# Bending_Machine_SCH.net
KiCad netlist of a schematic drawn in Altium Designer
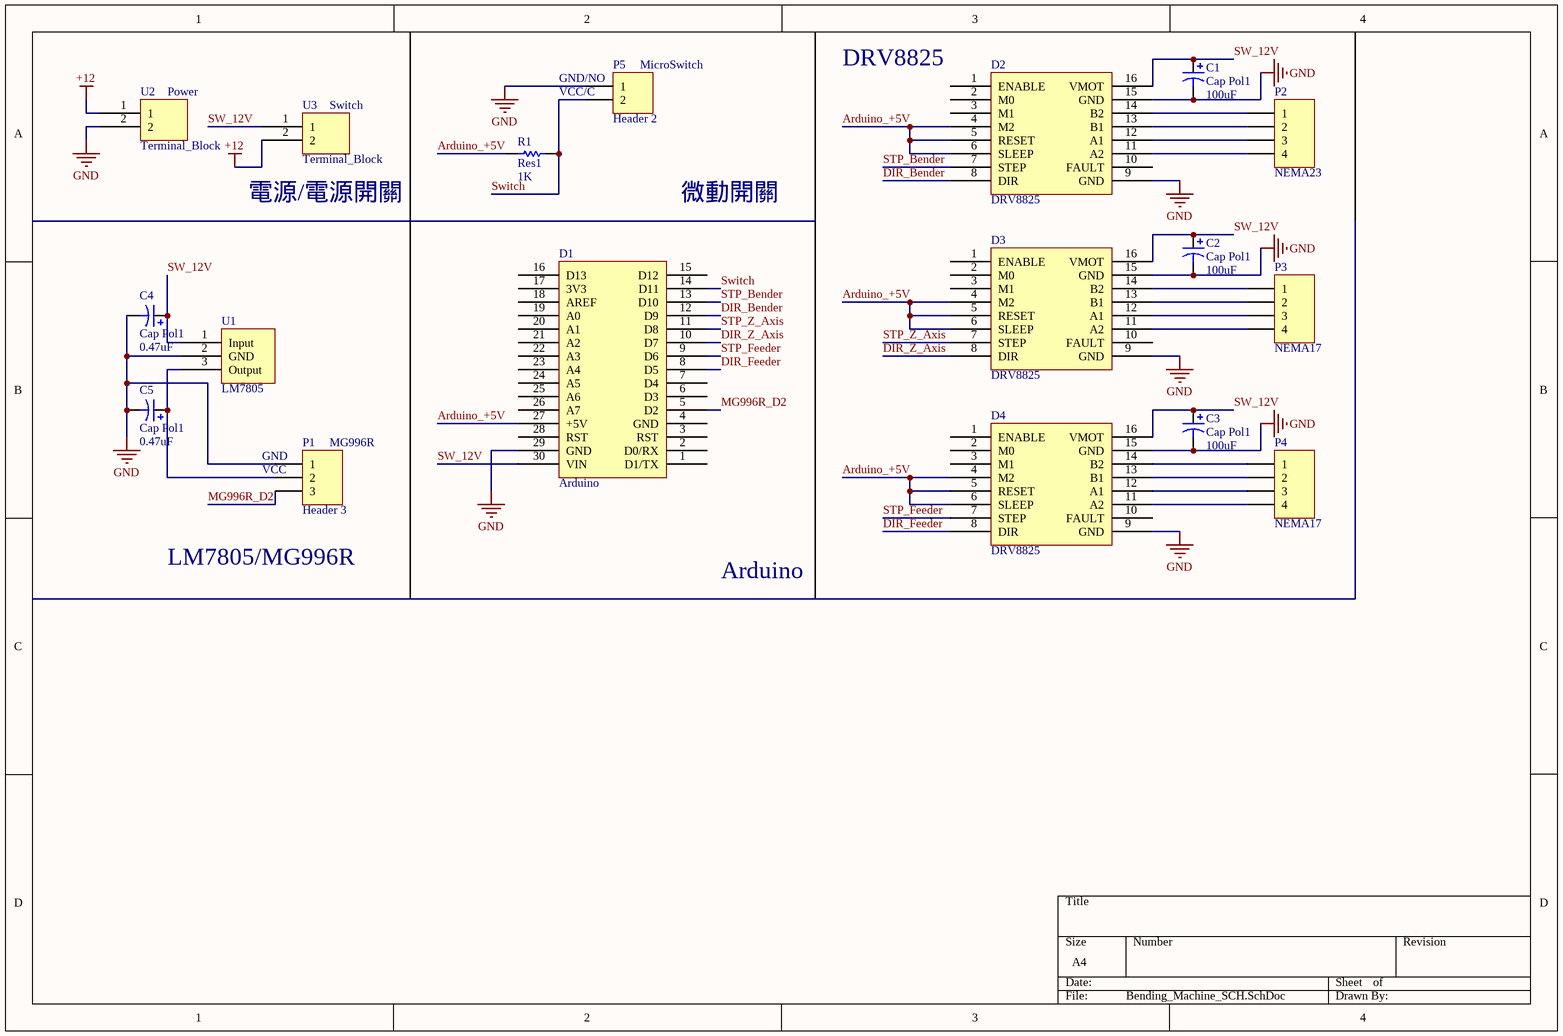
[diagram p0: Bending_Machine_SCH.SchDoc]

(export (version "E")
  (design (tool "Eeschema 10.0.6"))
  (components
    (comp (ref "C1")
      (value "Cap Pol1")
      (footprint "Cap_100uF")
      (description "Polarized Capacitor (Radial)")
      (fields (field (name "ALTIUM_VALUE") "100uF") (field (name "PUBLISHER") "Altium Limited"))
      (libsource (lib "Miscellaneous Devices") (part "Cap Pol1"))
    )
    (comp (ref "C2")
      (value "Cap Pol1")
      (footprint "Cap_100uF")
      (description "Polarized Capacitor (Radial)")
      (fields (field (name "ALTIUM_VALUE") "100uF") (field (name "PUBLISHER") "Altium Limited"))
      (libsource (lib "Miscellaneous Devices") (part "Cap Pol1"))
    )
    (comp (ref "C3")
      (value "Cap Pol1")
      (footprint "Cap_100uF")
      (description "Polarized Capacitor (Radial)")
      (fields (field (name "ALTIUM_VALUE") "100uF") (field (name "PUBLISHER") "Altium Limited"))
      (libsource (lib "Miscellaneous Devices") (part "Cap Pol1"))
    )
    (comp (ref "C4")
      (value "Cap Pol1")
      (footprint "Cap_0.47uF")
      (description "Polarized Capacitor (Radial)")
      (fields (field (name "ALTIUM_VALUE") "0.47uF") (field (name "PUBLISHER") "Altium Limited"))
      (libsource (lib "Miscellaneous Devices") (part "Cap Pol1"))
    )
    (comp (ref "C5")
      (value "Cap Pol1")
      (footprint "Cap_0.47uF")
      (description "Polarized Capacitor (Radial)")
      (fields (field (name "ALTIUM_VALUE") "0.47uF") (field (name "PUBLISHER") "Altium Limited"))
      (libsource (lib "Miscellaneous Devices") (part "Cap Pol1"))
    )
    (comp (ref "D1")
      (value "Arduino")
      (footprint "Arduino")
      (libsource (lib "Bending_Machine") (part "Arduino"))
    )
    (comp (ref "D2")
      (value "DRV8825")
      (footprint "DRV8825")
      (libsource (lib "Bending_Machine") (part "DRV8825"))
    )
    (comp (ref "D3")
      (value "DRV8825")
      (footprint "DRV8825")
      (libsource (lib "Bending_Machine") (part "DRV8825"))
    )
    (comp (ref "D4")
      (value "DRV8825")
      (footprint "DRV8825")
      (libsource (lib "Bending_Machine") (part "DRV8825"))
    )
    (comp (ref "P1")
      (value "Header 3")
      (footprint "HDR1X3")
      (description "Header, 3-Pin")
      (fields (field (name "PUBLISHER") "Altium Limited"))
      (libsource (lib "Miscellaneous Connectors") (part "Header 3"))
    )
    (comp (ref "P2")
      (value "NEMA23")
      (footprint "HDR1X4")
      (description "Header, 4-Pin")
      (fields (field (name "PUBLISHER") "Altium Limited"))
      (libsource (lib "Miscellaneous Connectors") (part "Header 4"))
    )
    (comp (ref "P3")
      (value "NEMA17")
      (footprint "HDR1X4")
      (description "Header, 4-Pin")
      (fields (field (name "PUBLISHER") "Altium Limited"))
      (libsource (lib "Miscellaneous Connectors") (part "Header 4"))
    )
    (comp (ref "P4")
      (value "NEMA17")
      (footprint "HDR1X4")
      (description "Header, 4-Pin")
      (fields (field (name "PUBLISHER") "Altium Limited"))
      (libsource (lib "Miscellaneous Connectors") (part "Header 4"))
    )
    (comp (ref "P5")
      (value "Header 2")
      (footprint "HDR1X2")
      (description "Header, 2-Pin")
      (fields (field (name "PUBLISHER") "Altium Limited"))
      (libsource (lib "Miscellaneous Connectors") (part "Header 2"))
    )
    (comp (ref "R1")
      (value "Res1")
      (footprint "AXIAL-0.3")
      (description "Resistor")
      (fields (field (name "ALTIUM_VALUE") "1K") (field (name "PUBLISHER") "Altium Limited"))
      (libsource (lib "Miscellaneous Devices") (part "Res1"))
    )
    (comp (ref "U1")
      (value "LM7805")
      (footprint "LM7805")
      (libsource (lib "Bending_Machine") (part "LM7805"))
    )
    (comp (ref "U2")
      (value "Terminal_Block")
      (footprint "terminal block")
      (libsource (lib "Bending_Machine") (part "Terminal Block"))
    )
    (comp (ref "U3")
      (value "Terminal_Block")
      (footprint "terminal block")
      (libsource (lib "Bending_Machine") (part "Terminal Block"))
    )
  )
  (nets
    (net (code "1") (name "+12") (class "Default")
      (node (ref "U2") (pin "1") (pinfunction "1_1") (pintype "passive"))
      (node (ref "U3") (pin "2") (pinfunction "2_2") (pintype "passive"))
    )
    (net (code "2") (name "/Arduino_+5V") (class "Default")
      (node (ref "D1") (pin "27") (pinfunction "+5V_27") (pintype "passive"))
      (node (ref "D2") (pin "4") (pinfunction "M2_4") (pintype "passive"))
      (node (ref "D2") (pin "5") (pinfunction "RESET_5") (pintype "passive"))
      (node (ref "D2") (pin "6") (pinfunction "SLEEP_6") (pintype "passive"))
      (node (ref "D3") (pin "4") (pinfunction "M2_4") (pintype "passive"))
      (node (ref "D3") (pin "5") (pinfunction "RESET_5") (pintype "passive"))
      (node (ref "D3") (pin "6") (pinfunction "SLEEP_6") (pintype "passive"))
      (node (ref "D4") (pin "4") (pinfunction "M2_4") (pintype "passive"))
      (node (ref "D4") (pin "5") (pinfunction "RESET_5") (pintype "passive"))
      (node (ref "D4") (pin "6") (pinfunction "SLEEP_6") (pintype "passive"))
      (node (ref "R1") (pin "1") (pinfunction "1_1") (pintype "passive"))
    )
    (net (code "3") (name "/DIR_Bender") (class "Default")
      (node (ref "D1") (pin "12") (pinfunction "D9_12") (pintype "passive"))
      (node (ref "D2") (pin "8") (pinfunction "DIR_8") (pintype "passive"))
    )
    (net (code "4") (name "/DIR_Feeder") (class "Default")
      (node (ref "D1") (pin "8") (pinfunction "D5_8") (pintype "passive"))
      (node (ref "D4") (pin "8") (pinfunction "DIR_8") (pintype "passive"))
    )
    (net (code "5") (name "/DIR_Z_Axis") (class "Default")
      (node (ref "D1") (pin "10") (pinfunction "D7_10") (pintype "passive"))
      (node (ref "D3") (pin "8") (pinfunction "DIR_8") (pintype "passive"))
    )
    (net (code "6") (name "/MG996R_D2") (class "Default")
      (node (ref "D1") (pin "5") (pinfunction "D2_5") (pintype "passive"))
      (node (ref "P1") (pin "3") (pinfunction "3_3") (pintype "passive"))
    )
    (net (code "7") (name "/STP_Bender") (class "Default")
      (node (ref "D1") (pin "13") (pinfunction "D10_13") (pintype "passive"))
      (node (ref "D2") (pin "7") (pinfunction "STEP_7") (pintype "passive"))
    )
    (net (code "8") (name "/STP_Feeder") (class "Default")
      (node (ref "D1") (pin "9") (pinfunction "D6_9") (pintype "passive"))
      (node (ref "D4") (pin "7") (pinfunction "STEP_7") (pintype "passive"))
    )
    (net (code "9") (name "/STP_Z_Axis") (class "Default")
      (node (ref "D1") (pin "11") (pinfunction "D8_11") (pintype "passive"))
      (node (ref "D3") (pin "7") (pinfunction "STEP_7") (pintype "passive"))
    )
    (net (code "10") (name "/SW_12V") (class "Default")
      (node (ref "C1") (pin "1") (pinfunction "1_1") (pintype "passive"))
      (node (ref "C2") (pin "1") (pinfunction "1_1") (pintype "passive"))
      (node (ref "C3") (pin "1") (pinfunction "1_1") (pintype "passive"))
      (node (ref "C4") (pin "1") (pinfunction "1_1") (pintype "passive"))
      (node (ref "D1") (pin "30") (pinfunction "VIN_30") (pintype "passive"))
      (node (ref "D2") (pin "16") (pinfunction "VMOT_16") (pintype "passive"))
      (node (ref "D3") (pin "16") (pinfunction "VMOT_16") (pintype "passive"))
      (node (ref "D4") (pin "16") (pinfunction "VMOT_16") (pintype "passive"))
      (node (ref "U1") (pin "1") (pinfunction "Input_1") (pintype "passive"))
      (node (ref "U3") (pin "1") (pinfunction "1_1") (pintype "passive"))
    )
    (net (code "11") (name "/Switch") (class "Default")
      (node (ref "D1") (pin "14") (pinfunction "D11_14") (pintype "passive"))
      (node (ref "P5") (pin "2") (pinfunction "2_2") (pintype "passive"))
      (node (ref "R1") (pin "2") (pinfunction "2_2") (pintype "passive"))
    )
    (net (code "12") (name "GND") (class "Default")
      (node (ref "C1") (pin "2") (pinfunction "2_2") (pintype "passive"))
      (node (ref "C2") (pin "2") (pinfunction "2_2") (pintype "passive"))
      (node (ref "C3") (pin "2") (pinfunction "2_2") (pintype "passive"))
      (node (ref "C4") (pin "2") (pinfunction "2_2") (pintype "passive"))
      (node (ref "C5") (pin "2") (pinfunction "2_2") (pintype "passive"))
      (node (ref "D1") (pin "29") (pinfunction "GND_29") (pintype "passive"))
      (node (ref "D2") (pin "15") (pinfunction "GND_15") (pintype "passive"))
      (node (ref "D2") (pin "9") (pinfunction "GND_9") (pintype "passive"))
      (node (ref "D3") (pin "15") (pinfunction "GND_15") (pintype "passive"))
      (node (ref "D3") (pin "9") (pinfunction "GND_9") (pintype "passive"))
      (node (ref "D4") (pin "15") (pinfunction "GND_15") (pintype "passive"))
      (node (ref "D4") (pin "9") (pinfunction "GND_9") (pintype "passive"))
      (node (ref "P1") (pin "1") (pinfunction "1_1") (pintype "passive"))
      (node (ref "P5") (pin "1") (pinfunction "1_1") (pintype "passive"))
      (node (ref "U1") (pin "2") (pinfunction "GND_2") (pintype "passive"))
      (node (ref "U2") (pin "2") (pinfunction "2_2") (pintype "passive"))
    )
    (net (code "13") (name "Net-(D2-A1)") (class "Default")
      (node (ref "D2") (pin "12") (pinfunction "A1_12") (pintype "passive"))
      (node (ref "P2") (pin "3") (pinfunction "3_3") (pintype "passive"))
    )
    (net (code "14") (name "Net-(D2-A2)") (class "Default")
      (node (ref "D2") (pin "11") (pinfunction "A2_11") (pintype "passive"))
      (node (ref "P2") (pin "4") (pinfunction "4_4") (pintype "passive"))
    )
    (net (code "15") (name "Net-(D2-B1)") (class "Default")
      (node (ref "D2") (pin "13") (pinfunction "B1_13") (pintype "passive"))
      (node (ref "P2") (pin "2") (pinfunction "2_2") (pintype "passive"))
    )
    (net (code "16") (name "Net-(D2-B2)") (class "Default")
      (node (ref "D2") (pin "14") (pinfunction "B2_14") (pintype "passive"))
      (node (ref "P2") (pin "1") (pinfunction "1_1") (pintype "passive"))
    )
    (net (code "17") (name "Net-(D3-A1)") (class "Default")
      (node (ref "D3") (pin "12") (pinfunction "A1_12") (pintype "passive"))
      (node (ref "P3") (pin "3") (pinfunction "3_3") (pintype "passive"))
    )
    (net (code "18") (name "Net-(D3-A2)") (class "Default")
      (node (ref "D3") (pin "11") (pinfunction "A2_11") (pintype "passive"))
      (node (ref "P3") (pin "4") (pinfunction "4_4") (pintype "passive"))
    )
    (net (code "19") (name "Net-(D3-B1)") (class "Default")
      (node (ref "D3") (pin "13") (pinfunction "B1_13") (pintype "passive"))
      (node (ref "P3") (pin "2") (pinfunction "2_2") (pintype "passive"))
    )
    (net (code "20") (name "Net-(D3-B2)") (class "Default")
      (node (ref "D3") (pin "14") (pinfunction "B2_14") (pintype "passive"))
      (node (ref "P3") (pin "1") (pinfunction "1_1") (pintype "passive"))
    )
    (net (code "21") (name "Net-(D4-A1)") (class "Default")
      (node (ref "D4") (pin "12") (pinfunction "A1_12") (pintype "passive"))
      (node (ref "P4") (pin "3") (pinfunction "3_3") (pintype "passive"))
    )
    (net (code "22") (name "Net-(D4-A2)") (class "Default")
      (node (ref "D4") (pin "11") (pinfunction "A2_11") (pintype "passive"))
      (node (ref "P4") (pin "4") (pinfunction "4_4") (pintype "passive"))
    )
    (net (code "23") (name "Net-(D4-B1)") (class "Default")
      (node (ref "D4") (pin "13") (pinfunction "B1_13") (pintype "passive"))
      (node (ref "P4") (pin "2") (pinfunction "2_2") (pintype "passive"))
    )
    (net (code "24") (name "Net-(D4-B2)") (class "Default")
      (node (ref "D4") (pin "14") (pinfunction "B2_14") (pintype "passive"))
      (node (ref "P4") (pin "1") (pinfunction "1_1") (pintype "passive"))
    )
    (net (code "25") (name "Net-(U1-Output)") (class "Default")
      (node (ref "C5") (pin "1") (pinfunction "1_1") (pintype "passive"))
      (node (ref "P1") (pin "2") (pinfunction "2_2") (pintype "passive"))
      (node (ref "U1") (pin "3") (pinfunction "Output_3") (pintype "passive"))
    )
    (net (code "26") (name "unconnected-(D1-3V3-Pad17)") (class "Default")
      (node (ref "D1") (pin "17") (pinfunction "3V3_17") (pintype "passive"))
    )
    (net (code "27") (name "unconnected-(D1-A0-Pad19)") (class "Default")
      (node (ref "D1") (pin "19") (pinfunction "A0_19") (pintype "passive"))
    )
    (net (code "28") (name "unconnected-(D1-A1-Pad20)") (class "Default")
      (node (ref "D1") (pin "20") (pinfunction "A1_20") (pintype "passive"))
    )
    (net (code "29") (name "unconnected-(D1-A2-Pad21)") (class "Default")
      (node (ref "D1") (pin "21") (pinfunction "A2_21") (pintype "passive"))
    )
    (net (code "30") (name "unconnected-(D1-A3-Pad22)") (class "Default")
      (node (ref "D1") (pin "22") (pinfunction "A3_22") (pintype "passive"))
    )
    (net (code "31") (name "unconnected-(D1-A4-Pad23)") (class "Default")
      (node (ref "D1") (pin "23") (pinfunction "A4_23") (pintype "passive"))
    )
    (net (code "32") (name "unconnected-(D1-A5-Pad24)") (class "Default")
      (node (ref "D1") (pin "24") (pinfunction "A5_24") (pintype "passive"))
    )
    (net (code "33") (name "unconnected-(D1-A6-Pad25)") (class "Default")
      (node (ref "D1") (pin "25") (pinfunction "A6_25") (pintype "passive"))
    )
    (net (code "34") (name "unconnected-(D1-A7-Pad26)") (class "Default")
      (node (ref "D1") (pin "26") (pinfunction "A7_26") (pintype "passive"))
    )
    (net (code "35") (name "unconnected-(D1-AREF-Pad18)") (class "Default")
      (node (ref "D1") (pin "18") (pinfunction "AREF_18") (pintype "passive"))
    )
    (net (code "36") (name "unconnected-(D1-D0{slash}RX-Pad2)") (class "Default")
      (node (ref "D1") (pin "2") (pinfunction "D0/RX_2") (pintype "passive"))
    )
    (net (code "37") (name "unconnected-(D1-D1{slash}TX-Pad1)") (class "Default")
      (node (ref "D1") (pin "1") (pinfunction "D1/TX_1") (pintype "passive"))
    )
    (net (code "38") (name "unconnected-(D1-D3-Pad6)") (class "Default")
      (node (ref "D1") (pin "6") (pinfunction "D3_6") (pintype "passive"))
    )
    (net (code "39") (name "unconnected-(D1-D4-Pad7)") (class "Default")
      (node (ref "D1") (pin "7") (pinfunction "D4_7") (pintype "passive"))
    )
    (net (code "40") (name "unconnected-(D1-D12-Pad15)") (class "Default")
      (node (ref "D1") (pin "15") (pinfunction "D12_15") (pintype "passive"))
    )
    (net (code "41") (name "unconnected-(D1-D13-Pad16)") (class "Default")
      (node (ref "D1") (pin "16") (pinfunction "D13_16") (pintype "passive"))
    )
    (net (code "42") (name "unconnected-(D1-GND-Pad4)") (class "Default")
      (node (ref "D1") (pin "4") (pinfunction "GND_4") (pintype "passive"))
    )
    (net (code "43") (name "unconnected-(D1-RST-Pad3)") (class "Default")
      (node (ref "D1") (pin "3") (pinfunction "RST_3") (pintype "passive"))
    )
    (net (code "44") (name "unconnected-(D1-RST-Pad28)") (class "Default")
      (node (ref "D1") (pin "28") (pinfunction "RST_28") (pintype "passive"))
    )
    (net (code "45") (name "unconnected-(D2-ENABLE-Pad1)") (class "Default")
      (node (ref "D2") (pin "1") (pinfunction "ENABLE_1") (pintype "passive"))
    )
    (net (code "46") (name "unconnected-(D2-FAULT-Pad10)") (class "Default")
      (node (ref "D2") (pin "10") (pinfunction "FAULT_10") (pintype "passive"))
    )
    (net (code "47") (name "unconnected-(D2-M0-Pad2)") (class "Default")
      (node (ref "D2") (pin "2") (pinfunction "M0_2") (pintype "passive"))
    )
    (net (code "48") (name "unconnected-(D2-M1-Pad3)") (class "Default")
      (node (ref "D2") (pin "3") (pinfunction "M1_3") (pintype "passive"))
    )
    (net (code "49") (name "unconnected-(D3-ENABLE-Pad1)") (class "Default")
      (node (ref "D3") (pin "1") (pinfunction "ENABLE_1") (pintype "passive"))
    )
    (net (code "50") (name "unconnected-(D3-FAULT-Pad10)") (class "Default")
      (node (ref "D3") (pin "10") (pinfunction "FAULT_10") (pintype "passive"))
    )
    (net (code "51") (name "unconnected-(D3-M0-Pad2)") (class "Default")
      (node (ref "D3") (pin "2") (pinfunction "M0_2") (pintype "passive"))
    )
    (net (code "52") (name "unconnected-(D3-M1-Pad3)") (class "Default")
      (node (ref "D3") (pin "3") (pinfunction "M1_3") (pintype "passive"))
    )
    (net (code "53") (name "unconnected-(D4-ENABLE-Pad1)") (class "Default")
      (node (ref "D4") (pin "1") (pinfunction "ENABLE_1") (pintype "passive"))
    )
    (net (code "54") (name "unconnected-(D4-FAULT-Pad10)") (class "Default")
      (node (ref "D4") (pin "10") (pinfunction "FAULT_10") (pintype "passive"))
    )
    (net (code "55") (name "unconnected-(D4-M0-Pad2)") (class "Default")
      (node (ref "D4") (pin "2") (pinfunction "M0_2") (pintype "passive"))
    )
    (net (code "56") (name "unconnected-(D4-M1-Pad3)") (class "Default")
      (node (ref "D4") (pin "3") (pinfunction "M1_3") (pintype "passive"))
    )
  )
)
